# Current_Sense.net
KiCad netlist of a schematic drawn in Altium Designer
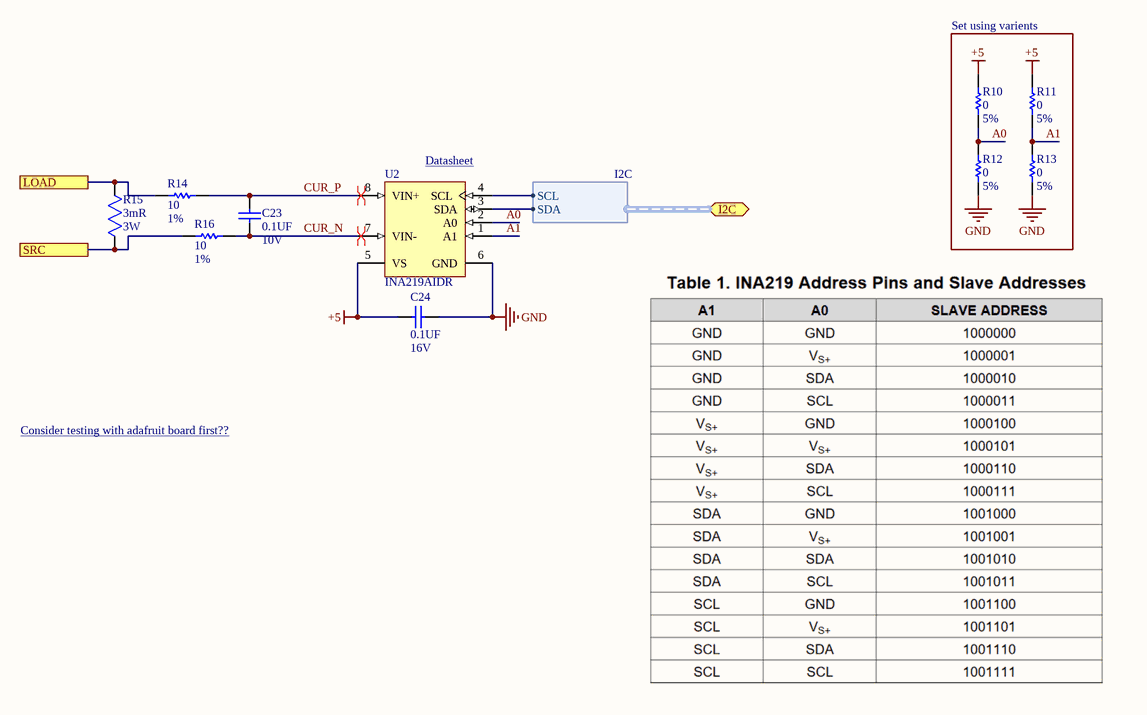
[diagram p0: Current Sense.SchDoc]

(export (version "E")
  (design (tool "Eeschema 10.0.6"))
  (components
    (comp (ref "C23")
      (value "CAP 0603 0.1UF 10V 10% X7R")
      (footprint "0603_CAP")
      (description "Capacitor Surface Mount 0603 Footprint 0.1UF 10V 10% Tolerance Ceramic X7R")
      (fields
        (field (name "VAL") "0.1UF")
        (field (name "VOL") "10V")
        (field (name "MANUFACTURER") "Various")
        (field (name "VOLTAGE") "10V")
      )
      (libsource (lib "Passive Components") (part "cap"))
    )
    (comp (ref "C24")
      (value "CAP 0603 0.1UF 16V 10% X7R")
      (footprint "0603_CAP")
      (description "Capacitor Surface Mount 0603 Footprint 0.1UF 16V 10% Tolerance Ceramic X7R")
      (fields
        (field (name "VAL") "0.1UF")
        (field (name "VOL") "16V")
        (field (name "MANUFACTURER") "Various")
        (field (name "VOLTAGE") "16V")
      )
      (libsource (lib "Passive Components") (part "cap"))
    )
    (comp (ref "R10")
      (value "RES 0603 0 5%")
      (footprint "0603_RES")
      (description "Resistor Surface Mount, 0 Ohms, 0603 Footprint, 5% Tolerance 0.1W")
      (fields
        (field (name "VAL") "0")
        (field (name "TOL") "5%")
        (field (name "MANUFACTURER") "Various")
        (field (name "TOLERANCE") "5%")
      )
      (libsource (lib "Passive Components") (part "res"))
    )
    (comp (ref "R11")
      (value "RES 0603 0 5%")
      (footprint "0603_RES")
      (description "Resistor Surface Mount, 0 Ohms, 0603 Footprint, 5% Tolerance 0.1W")
      (fields
        (field (name "VAL") "0")
        (field (name "TOL") "5%")
        (field (name "MANUFACTURER") "Various")
        (field (name "TOLERANCE") "5%")
      )
      (libsource (lib "Passive Components") (part "res"))
    )
    (comp (ref "R12")
      (value "RES 0603 0 5%")
      (footprint "0603_RES")
      (description "Resistor Surface Mount, 0 Ohms, 0603 Footprint, 5% Tolerance 0.1W")
      (fields
        (field (name "VAL") "0")
        (field (name "TOL") "5%")
        (field (name "MANUFACTURER") "Various")
        (field (name "TOLERANCE") "5%")
      )
      (libsource (lib "Passive Components") (part "res"))
    )
    (comp (ref "R13")
      (value "RES 0603 0 5%")
      (footprint "0603_RES")
      (description "Resistor Surface Mount, 0 Ohms, 0603 Footprint, 5% Tolerance 0.1W")
      (fields
        (field (name "VAL") "0")
        (field (name "TOL") "5%")
        (field (name "MANUFACTURER") "Various")
        (field (name "TOLERANCE") "5%")
      )
      (libsource (lib "Passive Components") (part "res"))
    )
    (comp (ref "R14")
      (value "RES 0603 10 1%")
      (footprint "0603_RES")
      (description "Resistor Surface Mount, 10 Ohms, 0603 Footprint, 1% Tolerance 0.1W")
      (fields
        (field (name "VAL") "10")
        (field (name "TOL") "1%")
        (field (name "MANUFACTURER") "Various")
        (field (name "TOLERANCE") "1%")
      )
      (libsource (lib "Passive Components") (part "res"))
    )
    (comp (ref "R15")
      (value "KRL6432E-M-R003-F-T1")
      (footprint "RES_6432-M")
      (fields
        (field (name "MANUFACTURER") "Susumu")
        (field (name "TOLERANCE") "1%")
        (field (name "RESISTANCE") "3mR")
        (field (name "POWER RATING") "3W")
      )
      (libsource (lib "AERO Parts") (part "KRL6432E-M-R003-F-T1"))
    )
    (comp (ref "R16")
      (value "RES 0603 10 1%")
      (footprint "0603_RES")
      (description "Resistor Surface Mount, 10 Ohms, 0603 Footprint, 1% Tolerance 0.1W")
      (fields
        (field (name "VAL") "10")
        (field (name "TOL") "1%")
        (field (name "MANUFACTURER") "Various")
        (field (name "TOLERANCE") "1%")
      )
      (libsource (lib "Passive Components") (part "res"))
    )
    (comp (ref "U2")
      (value "INA219AIDR")
      (footprint "D0008A_N")
      (fields (field (name "MANUFACTURER") "Texas Instruments"))
      (libsource (lib "AERO Parts") (part "INA219AIDR"))
    )
  )
  (nets
    (net (code "2") (name "+5") (class "Default")
      (node (ref "C24") (pin "1") (pinfunction "1_1") (pintype "passive"))
      (node (ref "R10") (pin "2") (pinfunction "2_2") (pintype "passive"))
      (node (ref "R11") (pin "2") (pinfunction "2_2") (pintype "passive"))
      (node (ref "U2") (pin "5") (pinfunction "VS_5") (pintype "power_in"))
    )
    (net (code "3") (name "/A0") (class "Default")
      (node (ref "R10") (pin "1") (pinfunction "1_1") (pintype "passive"))
      (node (ref "R12") (pin "2") (pinfunction "2_2") (pintype "passive"))
      (node (ref "U2") (pin "2") (pinfunction "A0_2") (pintype "input"))
    )
    (net (code "4") (name "/A1") (class "Default")
      (node (ref "R11") (pin "1") (pinfunction "1_1") (pintype "passive"))
      (node (ref "R13") (pin "2") (pinfunction "2_2") (pintype "passive"))
      (node (ref "U2") (pin "1") (pinfunction "A1_1") (pintype "input"))
    )
    (net (code "5") (name "/CUR_N") (class "Default")
      (node (ref "C23") (pin "1") (pinfunction "1_1") (pintype "passive"))
      (node (ref "R16") (pin "2") (pinfunction "2_2") (pintype "passive"))
      (node (ref "U2") (pin "7") (pinfunction "VIN-_7") (pintype "input"))
    )
    (net (code "6") (name "/CUR_P") (class "Default")
      (node (ref "C23") (pin "2") (pinfunction "2_2") (pintype "passive"))
      (node (ref "R14") (pin "2") (pinfunction "2_2") (pintype "passive"))
      (node (ref "U2") (pin "8") (pinfunction "VIN+_8") (pintype "input"))
    )
    (net (code "7") (name "/LOAD") (class "Default")
      (node (ref "R14") (pin "1") (pinfunction "1_1") (pintype "passive"))
      (node (ref "R15") (pin "2") (pinfunction "2_2") (pintype "passive"))
    )
    (net (code "8") (name "/SCL") (class "Default")
      (node (ref "U2") (pin "4") (pinfunction "SCL_4") (pintype "input"))
    )
    (net (code "9") (name "/SDA") (class "Default")
      (node (ref "U2") (pin "3") (pinfunction "SDA_3") (pintype "bidirectional"))
    )
    (net (code "10") (name "/SRC") (class "Default")
      (node (ref "R15") (pin "1") (pinfunction "1_1") (pintype "passive"))
      (node (ref "R16") (pin "1") (pinfunction "1_1") (pintype "passive"))
    )
    (net (code "12") (name "GND") (class "Default")
      (node (ref "C24") (pin "2") (pinfunction "2_2") (pintype "passive"))
      (node (ref "R12") (pin "1") (pinfunction "1_1") (pintype "passive"))
      (node (ref "R13") (pin "1") (pinfunction "1_1") (pintype "passive"))
      (node (ref "U2") (pin "6") (pinfunction "GND_6") (pintype "power_in"))
    )
  )
)
